# SMI_Bank_12.net
KiCad netlist of a schematic drawn in Altium Designer
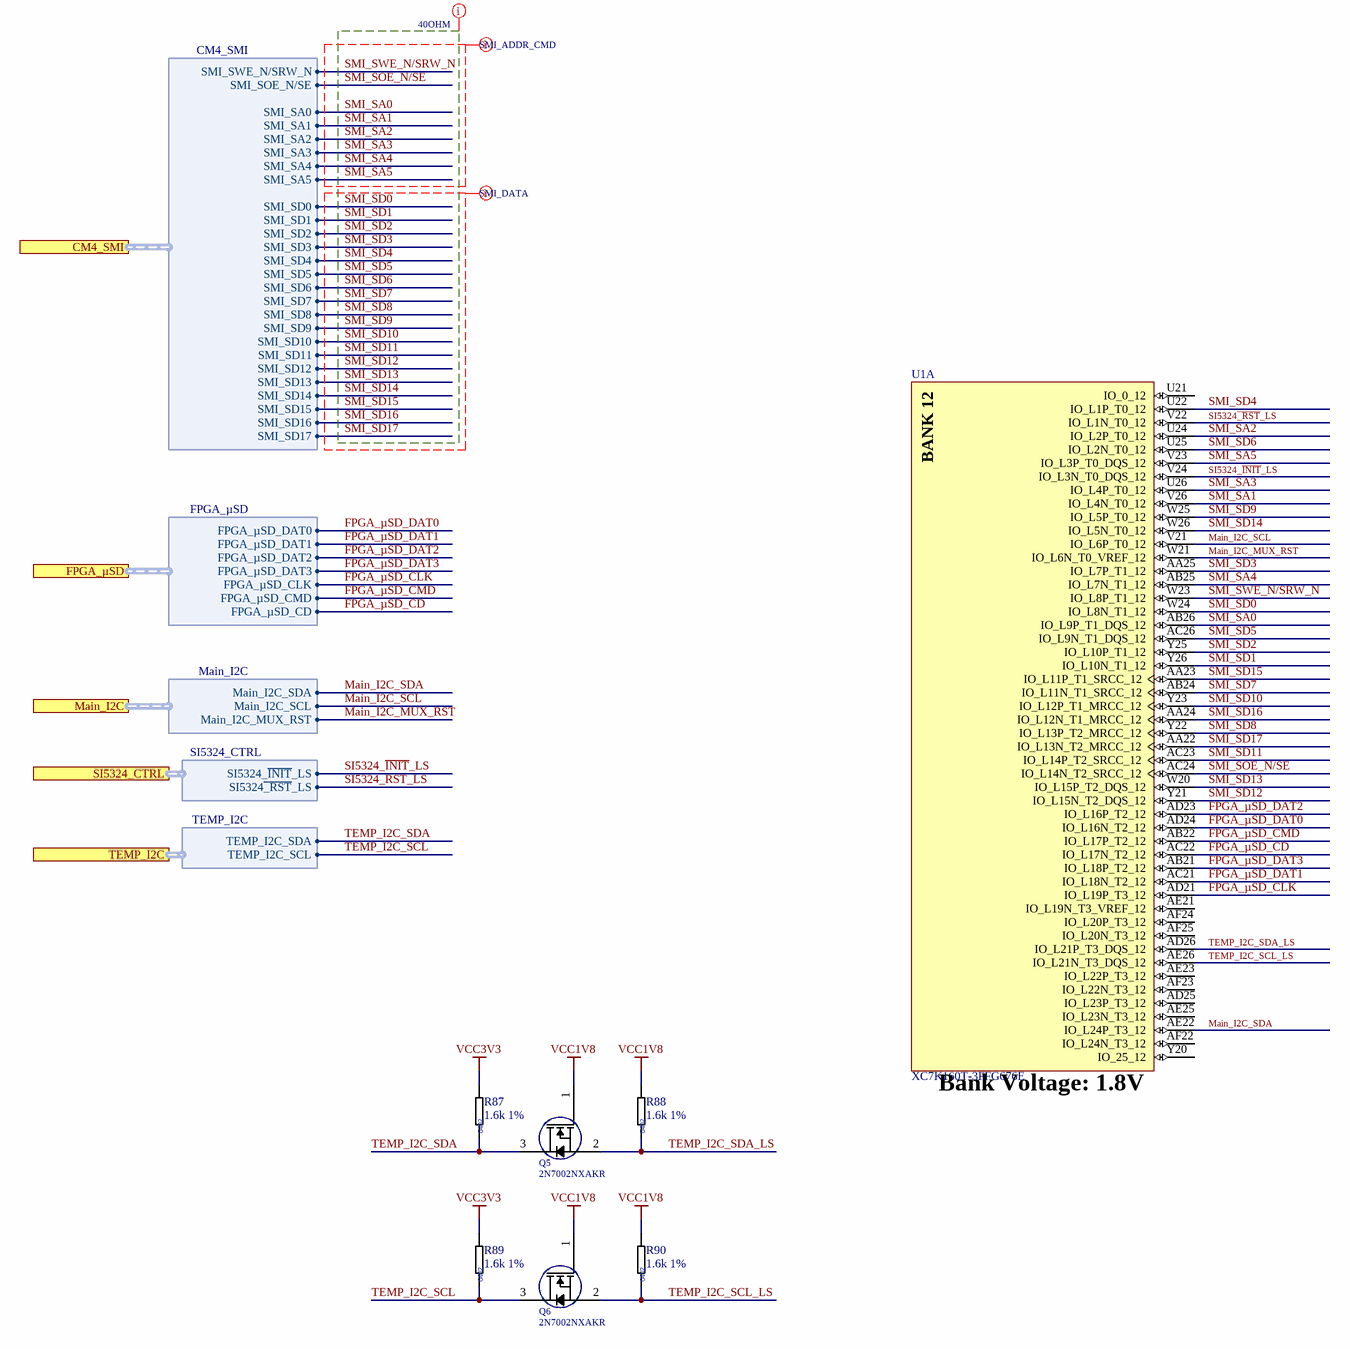
[diagram p0: SMI Bank 12.SchDoc]

(export (version "E")
  (design (tool "Eeschema 10.0.6"))
  (components
    (comp (ref "Q5")
      (value "2N7002NXAKR")
      (footprint "trans:SOT95P251X112-3N")
      (description "MOSFET 60V SGL N-CH TRENCHMOS")
      (libsource (lib "Trans") (part "2N7002NXAKR_MOSFET 60V SGL N-CH TRENCHMOS"))
    )
    (comp (ref "Q6")
      (value "2N7002NXAKR")
      (footprint "trans:SOT95P251X112-3N")
      (description "MOSFET 60V SGL N-CH TRENCHMOS")
      (libsource (lib "Trans") (part "2N7002NXAKR_MOSFET 60V SGL N-CH TRENCHMOS"))
    )
    (comp (ref "R87")
      (value "1.6k 1%")
      (footprint "RES_0402_L")
      (description "Thick Film Resistors - SMD 1.6kOhm 1%")
      (libsource (lib "Res") (part "RES_0402_1.6k_1%"))
    )
    (comp (ref "R88")
      (value "1.6k 1%")
      (footprint "RES_0402_L")
      (description "Thick Film Resistors - SMD 1.6kOhm 1%")
      (libsource (lib "Res") (part "RES_0402_1.6k_1%"))
    )
    (comp (ref "R89")
      (value "1.6k 1%")
      (footprint "RES_0402_L")
      (description "Thick Film Resistors - SMD 1.6kOhm 1%")
      (libsource (lib "Res") (part "RES_0402_1.6k_1%"))
    )
    (comp (ref "R90")
      (value "1.6k 1%")
      (footprint "RES_0402_L")
      (description "Thick Film Resistors - SMD 1.6kOhm 1%")
      (libsource (lib "Res") (part "RES_0402_1.6k_1%"))
    )
    (comp (ref "U1")
      (value "XC7K160T-3FFG676E")
      (footprint "Digital:BGA100P2700X2700X317-676N")
      (description "Kintex-7 FPGA, 400 User I/Os, 8 GTX, 676-Ball BGA, Speed Grade 3, Extended Grade, Pb-Free")
      (libsource (lib "Digital") (part "XC7K160T-3FFG676E_Kintex-7 FPGA, 400 User I/Os, 8 GTX, FFG676"))
    )
  )
  (nets
    (net (code "6") (name "/FPGA_µSD_CD") (class "Default")
      (node (ref "U1") (pin "AC22") (pinfunction "IO_L17N_T2_12_AC22") (pintype "bidirectional"))
    )
    (net (code "7") (name "/FPGA_µSD_CLK") (class "Default")
      (node (ref "U1") (pin "AD21") (pinfunction "IO_L19P_T3_12_AD21") (pintype "bidirectional"))
    )
    (net (code "8") (name "/FPGA_µSD_CMD") (class "Default")
      (node (ref "U1") (pin "AB22") (pinfunction "IO_L17P_T2_12_AB22") (pintype "bidirectional"))
    )
    (net (code "9") (name "/FPGA_µSD_DAT0") (class "Default")
      (node (ref "U1") (pin "AD24") (pinfunction "IO_L16N_T2_12_AD24") (pintype "bidirectional"))
    )
    (net (code "10") (name "/FPGA_µSD_DAT1") (class "Default")
      (node (ref "U1") (pin "AC21") (pinfunction "IO_L18N_T2_12_AC21") (pintype "bidirectional"))
    )
    (net (code "11") (name "/FPGA_µSD_DAT2") (class "Default")
      (node (ref "U1") (pin "AD23") (pinfunction "IO_L16P_T2_12_AD23") (pintype "bidirectional"))
    )
    (net (code "12") (name "/FPGA_µSD_DAT3") (class "Default")
      (node (ref "U1") (pin "AB21") (pinfunction "IO_L18P_T2_12_AB21") (pintype "bidirectional"))
    )
    (net (code "13") (name "/Main_I2C_MUX_RST") (class "Default")
      (node (ref "U1") (pin "W21") (pinfunction "IO_L6N_T0_VREF_12_W21") (pintype "bidirectional"))
    )
    (net (code "14") (name "/Main_I2C_SCL") (class "Default")
      (node (ref "U1") (pin "V21") (pinfunction "IO_L6P_T0_12_V21") (pintype "bidirectional"))
    )
    (net (code "15") (name "/Main_I2C_SDA") (class "Default")
      (node (ref "U1") (pin "AE22") (pinfunction "IO_L24P_T3_12_AE22") (pintype "bidirectional"))
    )
    (net (code "16") (name "/SI5324_~{INIT}_LS") (class "Default")
      (node (ref "U1") (pin "V24") (pinfunction "IO_L3N_T0_DQS_12_V24") (pintype "bidirectional"))
    )
    (net (code "17") (name "/SI5324~{_RST}_LS") (class "Default")
      (node (ref "U1") (pin "V22") (pinfunction "IO_L1N_T0_12_V22") (pintype "bidirectional"))
    )
    (net (code "18") (name "/SMI_SA0") (class "Default")
      (node (ref "U1") (pin "AB26") (pinfunction "IO_L9P_T1_DQS_12_AB26") (pintype "bidirectional"))
    )
    (net (code "19") (name "/SMI_SA1") (class "Default")
      (node (ref "U1") (pin "V26") (pinfunction "IO_L4N_T0_12_V26") (pintype "bidirectional"))
    )
    (net (code "20") (name "/SMI_SA2") (class "Default")
      (node (ref "U1") (pin "U24") (pinfunction "IO_L2P_T0_12_U24") (pintype "bidirectional"))
    )
    (net (code "21") (name "/SMI_SA3") (class "Default")
      (node (ref "U1") (pin "U26") (pinfunction "IO_L4P_T0_12_U26") (pintype "bidirectional"))
    )
    (net (code "22") (name "/SMI_SA4") (class "Default")
      (node (ref "U1") (pin "AB25") (pinfunction "IO_L7N_T1_12_AB25") (pintype "bidirectional"))
    )
    (net (code "23") (name "/SMI_SA5") (class "Default")
      (node (ref "U1") (pin "V23") (pinfunction "IO_L3P_T0_DQS_12_V23") (pintype "bidirectional"))
    )
    (net (code "24") (name "/SMI_SD0") (class "Default")
      (node (ref "U1") (pin "W24") (pinfunction "IO_L8N_T1_12_W24") (pintype "bidirectional"))
    )
    (net (code "25") (name "/SMI_SD1") (class "Default")
      (node (ref "U1") (pin "Y26") (pinfunction "IO_L10N_T1_12_Y26") (pintype "bidirectional"))
    )
    (net (code "26") (name "/SMI_SD2") (class "Default")
      (node (ref "U1") (pin "Y25") (pinfunction "IO_L10P_T1_12_Y25") (pintype "bidirectional"))
    )
    (net (code "27") (name "/SMI_SD3") (class "Default")
      (node (ref "U1") (pin "AA25") (pinfunction "IO_L7P_T1_12_AA25") (pintype "bidirectional"))
    )
    (net (code "28") (name "/SMI_SD4") (class "Default")
      (node (ref "U1") (pin "U22") (pinfunction "IO_L1P_T0_12_U22") (pintype "bidirectional"))
    )
    (net (code "29") (name "/SMI_SD5") (class "Default")
      (node (ref "U1") (pin "AC26") (pinfunction "IO_L9N_T1_DQS_12_AC26") (pintype "bidirectional"))
    )
    (net (code "30") (name "/SMI_SD6") (class "Default")
      (node (ref "U1") (pin "U25") (pinfunction "IO_L2N_T0_12_U25") (pintype "bidirectional"))
    )
    (net (code "31") (name "/SMI_SD7") (class "Default")
      (node (ref "U1") (pin "AB24") (pinfunction "IO_L11N_T1_SRCC_12_AB24") (pintype "bidirectional"))
    )
    (net (code "32") (name "/SMI_SD8") (class "Default")
      (node (ref "U1") (pin "Y22") (pinfunction "IO_L13P_T2_MRCC_12_Y22") (pintype "bidirectional"))
    )
    (net (code "33") (name "/SMI_SD9") (class "Default")
      (node (ref "U1") (pin "W25") (pinfunction "IO_L5P_T0_12_W25") (pintype "bidirectional"))
    )
    (net (code "34") (name "/SMI_SD10") (class "Default")
      (node (ref "U1") (pin "Y23") (pinfunction "IO_L12P_T1_MRCC_12_Y23") (pintype "bidirectional"))
    )
    (net (code "35") (name "/SMI_SD11") (class "Default")
      (node (ref "U1") (pin "AC23") (pinfunction "IO_L14P_T2_SRCC_12_AC23") (pintype "bidirectional"))
    )
    (net (code "36") (name "/SMI_SD12") (class "Default")
      (node (ref "U1") (pin "Y21") (pinfunction "IO_L15N_T2_DQS_12_Y21") (pintype "bidirectional"))
    )
    (net (code "37") (name "/SMI_SD13") (class "Default")
      (node (ref "U1") (pin "W20") (pinfunction "IO_L15P_T2_DQS_12_W20") (pintype "bidirectional"))
    )
    (net (code "38") (name "/SMI_SD14") (class "Default")
      (node (ref "U1") (pin "W26") (pinfunction "IO_L5N_T0_12_W26") (pintype "bidirectional"))
    )
    (net (code "39") (name "/SMI_SD15") (class "Default")
      (node (ref "U1") (pin "AA23") (pinfunction "IO_L11P_T1_SRCC_12_AA23") (pintype "bidirectional"))
    )
    (net (code "40") (name "/SMI_SD16") (class "Default")
      (node (ref "U1") (pin "AA24") (pinfunction "IO_L12N_T1_MRCC_12_AA24") (pintype "bidirectional"))
    )
    (net (code "41") (name "/SMI_SD17") (class "Default")
      (node (ref "U1") (pin "AA22") (pinfunction "IO_L13N_T2_MRCC_12_AA22") (pintype "bidirectional"))
    )
    (net (code "42") (name "/SMI_SOE_N{slash}SE") (class "Default")
      (node (ref "U1") (pin "AC24") (pinfunction "IO_L14N_T2_SRCC_12_AC24") (pintype "bidirectional"))
    )
    (net (code "43") (name "/SMI_SWE_N{slash}SRW_N") (class "Default")
      (node (ref "U1") (pin "W23") (pinfunction "IO_L8P_T1_12_W23") (pintype "bidirectional"))
    )
    (net (code "44") (name "/TEMP_I2C_SCL") (class "Default")
      (node (ref "Q6") (pin "3") (pinfunction "D_3") (pintype "passive"))
      (node (ref "R89") (pin "1") (pinfunction "1_1") (pintype "passive"))
    )
    (net (code "45") (name "/TEMP_I2C_SCL_LS") (class "Default")
      (node (ref "Q6") (pin "2") (pinfunction "S_2") (pintype "passive"))
      (node (ref "R90") (pin "1") (pinfunction "1_1") (pintype "passive"))
      (node (ref "U1") (pin "AE26") (pinfunction "IO_L21N_T3_DQS_12_AE26") (pintype "bidirectional"))
    )
    (net (code "46") (name "/TEMP_I2C_SDA") (class "Default")
      (node (ref "Q5") (pin "3") (pinfunction "D_3") (pintype "passive"))
      (node (ref "R87") (pin "1") (pinfunction "1_1") (pintype "passive"))
    )
    (net (code "47") (name "/TEMP_I2C_SDA_LS") (class "Default")
      (node (ref "Q5") (pin "2") (pinfunction "S_2") (pintype "passive"))
      (node (ref "R88") (pin "1") (pinfunction "1_1") (pintype "passive"))
      (node (ref "U1") (pin "AD26") (pinfunction "IO_L21P_T3_DQS_12_AD26") (pintype "bidirectional"))
    )
    (net (code "53") (name "VCC1V8") (class "Default")
      (node (ref "Q5") (pin "1") (pinfunction "G_1") (pintype "passive"))
      (node (ref "Q6") (pin "1") (pinfunction "G_1") (pintype "passive"))
      (node (ref "R88") (pin "2") (pinfunction "2_2") (pintype "passive"))
      (node (ref "R90") (pin "2") (pinfunction "2_2") (pintype "passive"))
    )
    (net (code "54") (name "VCC3V3") (class "Default")
      (node (ref "R87") (pin "2") (pinfunction "2_2") (pintype "passive"))
      (node (ref "R89") (pin "2") (pinfunction "2_2") (pintype "passive"))
    )
    (net (code "55") (name "unconnected-(U1A-IO_0_12-PadU21)") (class "Default")
      (node (ref "U1") (pin "U21") (pinfunction "IO_0_12_U21") (pintype "bidirectional"))
    )
    (net (code "56") (name "unconnected-(U1A-IO_25_12-PadY20)") (class "Default")
      (node (ref "U1") (pin "Y20") (pinfunction "IO_25_12_Y20") (pintype "bidirectional"))
    )
    (net (code "57") (name "unconnected-(U1A-IO_L19N_T3_VREF_12-PadAE21)") (class "Default")
      (node (ref "U1") (pin "AE21") (pinfunction "IO_L19N_T3_VREF_12_AE21") (pintype "bidirectional"))
    )
    (net (code "58") (name "unconnected-(U1A-IO_L20N_T3_12-PadAF25)") (class "Default")
      (node (ref "U1") (pin "AF25") (pinfunction "IO_L20N_T3_12_AF25") (pintype "bidirectional"))
    )
    (net (code "59") (name "unconnected-(U1A-IO_L20P_T3_12-PadAF24)") (class "Default")
      (node (ref "U1") (pin "AF24") (pinfunction "IO_L20P_T3_12_AF24") (pintype "bidirectional"))
    )
    (net (code "60") (name "unconnected-(U1A-IO_L22N_T3_12-PadAF23)") (class "Default")
      (node (ref "U1") (pin "AF23") (pinfunction "IO_L22N_T3_12_AF23") (pintype "bidirectional"))
    )
    (net (code "61") (name "unconnected-(U1A-IO_L22P_T3_12-PadAE23)") (class "Default")
      (node (ref "U1") (pin "AE23") (pinfunction "IO_L22P_T3_12_AE23") (pintype "bidirectional"))
    )
    (net (code "62") (name "unconnected-(U1A-IO_L23N_T3_12-PadAE25)") (class "Default")
      (node (ref "U1") (pin "AE25") (pinfunction "IO_L23N_T3_12_AE25") (pintype "bidirectional"))
    )
    (net (code "63") (name "unconnected-(U1A-IO_L23P_T3_12-PadAD25)") (class "Default")
      (node (ref "U1") (pin "AD25") (pinfunction "IO_L23P_T3_12_AD25") (pintype "bidirectional"))
    )
    (net (code "64") (name "unconnected-(U1A-IO_L24N_T3_12-PadAF22)") (class "Default")
      (node (ref "U1") (pin "AF22") (pinfunction "IO_L24N_T3_12_AF22") (pintype "bidirectional"))
    )
  )
)
